# BlackKnight.net
KiCad netlist of a schematic drawn in EAGLE
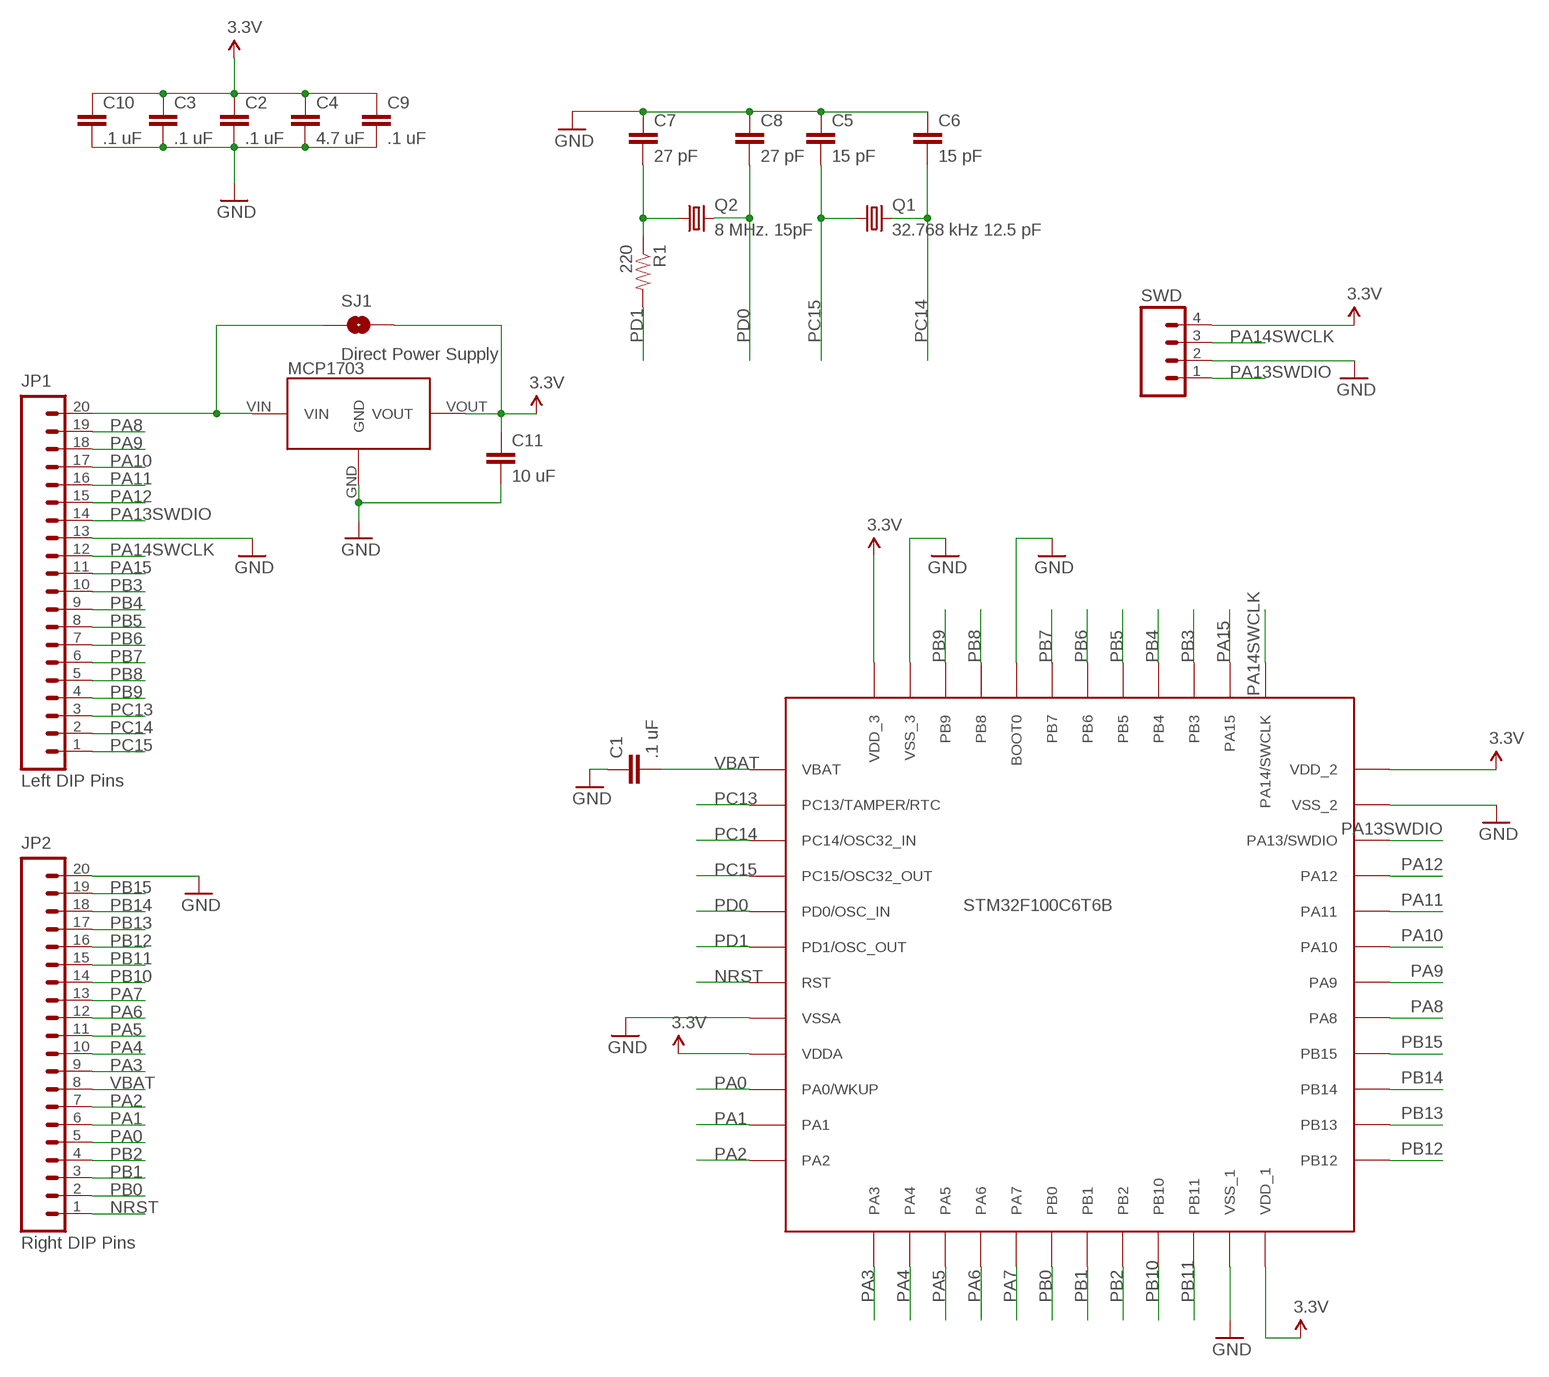
[diagram p0: schematic, sheet 1]

(export (version "E")
  (design (tool "Eeschema 10.0.6"))
  (components
    (comp (ref "C1")
      (value ".1 uF")
      (footprint "eagle-import:0805")
      (libsource (lib "eagle-import") (part "1.0UF-25V-+80/-20(0805)"))
    )
    (comp (ref "C2")
      (value ".1 uF")
      (footprint "eagle-import:0805")
      (libsource (lib "eagle-import") (part "1.0UF-25V-+80/-20(0805)"))
    )
    (comp (ref "C3")
      (value ".1 uF")
      (footprint "eagle-import:0805")
      (libsource (lib "eagle-import") (part "1.0UF-25V-+80/-20(0805)"))
    )
    (comp (ref "C4")
      (value "4.7 uF")
      (footprint "eagle-import:0805")
      (libsource (lib "eagle-import") (part "1.0UF-25V-+80/-20(0805)"))
    )
    (comp (ref "C5")
      (value "15 pF")
      (footprint "eagle-import:0805")
      (libsource (lib "eagle-import") (part "1.0UF-25V-+80/-20(0805)"))
    )
    (comp (ref "C6")
      (value "15 pF")
      (footprint "eagle-import:0805")
      (libsource (lib "eagle-import") (part "1.0UF-25V-+80/-20(0805)"))
    )
    (comp (ref "C7")
      (value "27 pF")
      (footprint "eagle-import:0805")
      (libsource (lib "eagle-import") (part "1.0UF-25V-+80/-20(0805)"))
    )
    (comp (ref "C8")
      (value "27 pF")
      (footprint "eagle-import:0805")
      (libsource (lib "eagle-import") (part "1.0UF-25V-+80/-20(0805)"))
    )
    (comp (ref "C9")
      (value ".1 uF")
      (footprint "eagle-import:0805")
      (libsource (lib "eagle-import") (part "1.0UF-25V-+80/-20(0805)"))
    )
    (comp (ref "C10")
      (value ".1 uF")
      (footprint "eagle-import:0805")
      (libsource (lib "eagle-import") (part "1.0UF-25V-+80/-20(0805)"))
    )
    (comp (ref "C11")
      (value "10 uF")
      (footprint "eagle-import:0805")
      (libsource (lib "eagle-import") (part "1.0UF-25V-+80/-20(0805)"))
    )
    (comp (ref "JP1")
      (value "Left DIP Pins")
      (footprint "eagle-import:1X20")
      (libsource (lib "eagle-import") (part "M20"))
    )
    (comp (ref "JP2")
      (value "Right DIP Pins")
      (footprint "eagle-import:1X20")
      (libsource (lib "eagle-import") (part "M20"))
    )
    (comp (ref "MCP1703")
      (value "MCP1703")
      (footprint "eagle-import:SOT-89")
      (libsource (lib "eagle-import") (part "MCP1703"))
    )
    (comp (ref "Q1")
      (value "32.768 kHz 12.5 pF")
      (footprint "eagle-import:TC26H")
      (libsource (lib "eagle-import") (part "CRYSTALTC26H"))
    )
    (comp (ref "Q2")
      (value "8 MHz. 15pF")
      (footprint "eagle-import:HC49U-V")
      (libsource (lib "eagle-import") (part "CRYSTALHC49U-V"))
    )
    (comp (ref "R1")
      (value "220")
      (footprint "eagle-import:0805")
      (libsource (lib "eagle-import") (part "RESISTOR0805-RES"))
    )
    (comp (ref "SJ1")
      (value "Direct Power Supply")
      (footprint "eagle-import:SJ_2S-NO")
      (libsource (lib "eagle-import") (part "SOLDERJUMPER-OLDNO"))
    )
    (comp (ref "STM32F100C6T6B")
      (value "STM32F100C6T6B")
      (footprint "eagle-import:48-LQFP")
      (libsource (lib "eagle-import") (part "STM32F100C6T6B"))
    )
    (comp (ref "SWD")
      (value "M04LOCK")
      (footprint "eagle-import:1X04_LOCK")
      (libsource (lib "eagle-import") (part "M04LOCK"))
    )
  )
  (nets
    (net (code "1") (name "/NRST") (class "Default")
      (node (ref "JP2") (pin "1") (pinfunction "1_1") (pintype "passive"))
      (node (ref "STM32F100C6T6B") (pin "RST") (pinfunction "RST_RST") (pintype "bidirectional"))
    )
    (net (code "2") (name "/PA0") (class "Default")
      (node (ref "JP2") (pin "5") (pinfunction "5_5") (pintype "passive"))
      (node (ref "STM32F100C6T6B") (pin "PA0/WKUP") (pinfunction "PA0/WKUP_PA0/WKUP") (pintype "bidirectional"))
    )
    (net (code "3") (name "/PA1") (class "Default")
      (node (ref "JP2") (pin "6") (pinfunction "6_6") (pintype "passive"))
      (node (ref "STM32F100C6T6B") (pin "PA1") (pinfunction "PA1_PA1") (pintype "bidirectional"))
    )
    (net (code "4") (name "/PA2") (class "Default")
      (node (ref "JP2") (pin "7") (pinfunction "7_7") (pintype "passive"))
      (node (ref "STM32F100C6T6B") (pin "PA2") (pinfunction "PA2_PA2") (pintype "bidirectional"))
    )
    (net (code "5") (name "/PA3") (class "Default")
      (node (ref "JP2") (pin "9") (pinfunction "9_9") (pintype "passive"))
      (node (ref "STM32F100C6T6B") (pin "PA3") (pinfunction "PA3_PA3") (pintype "bidirectional"))
    )
    (net (code "6") (name "/PA4") (class "Default")
      (node (ref "JP2") (pin "10") (pinfunction "10_10") (pintype "passive"))
      (node (ref "STM32F100C6T6B") (pin "PA4") (pinfunction "PA4_PA4") (pintype "bidirectional"))
    )
    (net (code "7") (name "/PA5") (class "Default")
      (node (ref "JP2") (pin "11") (pinfunction "11_11") (pintype "passive"))
      (node (ref "STM32F100C6T6B") (pin "PA5") (pinfunction "PA5_PA5") (pintype "bidirectional"))
    )
    (net (code "8") (name "/PA6") (class "Default")
      (node (ref "JP2") (pin "12") (pinfunction "12_12") (pintype "passive"))
      (node (ref "STM32F100C6T6B") (pin "PA6") (pinfunction "PA6_PA6") (pintype "bidirectional"))
    )
    (net (code "9") (name "/PA7") (class "Default")
      (node (ref "JP2") (pin "13") (pinfunction "13_13") (pintype "passive"))
      (node (ref "STM32F100C6T6B") (pin "PA7") (pinfunction "PA7_PA7") (pintype "bidirectional"))
    )
    (net (code "10") (name "/PA8") (class "Default")
      (node (ref "JP1") (pin "19") (pinfunction "19_19") (pintype "passive"))
      (node (ref "STM32F100C6T6B") (pin "PA8") (pinfunction "PA8_PA8") (pintype "bidirectional"))
    )
    (net (code "11") (name "/PA9") (class "Default")
      (node (ref "JP1") (pin "18") (pinfunction "18_18") (pintype "passive"))
      (node (ref "STM32F100C6T6B") (pin "PA9") (pinfunction "PA9_PA9") (pintype "bidirectional"))
    )
    (net (code "12") (name "/PA10") (class "Default")
      (node (ref "JP1") (pin "17") (pinfunction "17_17") (pintype "passive"))
      (node (ref "STM32F100C6T6B") (pin "PA10") (pinfunction "PA10_PA10") (pintype "bidirectional"))
    )
    (net (code "13") (name "/PA11") (class "Default")
      (node (ref "JP1") (pin "16") (pinfunction "16_16") (pintype "passive"))
      (node (ref "STM32F100C6T6B") (pin "PA11") (pinfunction "PA11_PA11") (pintype "bidirectional"))
    )
    (net (code "14") (name "/PA12") (class "Default")
      (node (ref "JP1") (pin "15") (pinfunction "15_15") (pintype "passive"))
      (node (ref "STM32F100C6T6B") (pin "PA12") (pinfunction "PA12_PA12") (pintype "bidirectional"))
    )
    (net (code "15") (name "/PA13SWDIO") (class "Default")
      (node (ref "JP1") (pin "14") (pinfunction "14_14") (pintype "passive"))
      (node (ref "STM32F100C6T6B") (pin "PA13/SWDIO") (pinfunction "PA13/SWDIO_PA13/SWDIO") (pintype "bidirectional"))
      (node (ref "SWD") (pin "1") (pinfunction "1_1") (pintype "passive"))
    )
    (net (code "16") (name "/PA14SWCLK") (class "Default")
      (node (ref "JP1") (pin "12") (pinfunction "12_12") (pintype "passive"))
      (node (ref "STM32F100C6T6B") (pin "PA14/SWCLK") (pinfunction "PA14/SWCLK_PA14/SWCLK") (pintype "bidirectional"))
      (node (ref "SWD") (pin "3") (pinfunction "3_3") (pintype "passive"))
    )
    (net (code "17") (name "/PA15") (class "Default")
      (node (ref "JP1") (pin "11") (pinfunction "11_11") (pintype "passive"))
      (node (ref "STM32F100C6T6B") (pin "PA15") (pinfunction "PA15_PA15") (pintype "bidirectional"))
    )
    (net (code "18") (name "/PB0") (class "Default")
      (node (ref "JP2") (pin "2") (pinfunction "2_2") (pintype "passive"))
      (node (ref "STM32F100C6T6B") (pin "PB0") (pinfunction "PB0_PB0") (pintype "bidirectional"))
    )
    (net (code "19") (name "/PB1") (class "Default")
      (node (ref "JP2") (pin "3") (pinfunction "3_3") (pintype "passive"))
      (node (ref "STM32F100C6T6B") (pin "PB1") (pinfunction "PB1_PB1") (pintype "bidirectional"))
    )
    (net (code "20") (name "/PB2") (class "Default")
      (node (ref "JP2") (pin "4") (pinfunction "4_4") (pintype "passive"))
      (node (ref "STM32F100C6T6B") (pin "PB2") (pinfunction "PB2_PB2") (pintype "bidirectional"))
    )
    (net (code "21") (name "/PB3") (class "Default")
      (node (ref "JP1") (pin "10") (pinfunction "10_10") (pintype "passive"))
      (node (ref "STM32F100C6T6B") (pin "PB3") (pinfunction "PB3_PB3") (pintype "bidirectional"))
    )
    (net (code "22") (name "/PB4") (class "Default")
      (node (ref "JP1") (pin "9") (pinfunction "9_9") (pintype "passive"))
      (node (ref "STM32F100C6T6B") (pin "PB4") (pinfunction "PB4_PB4") (pintype "bidirectional"))
    )
    (net (code "23") (name "/PB5") (class "Default")
      (node (ref "JP1") (pin "8") (pinfunction "8_8") (pintype "passive"))
      (node (ref "STM32F100C6T6B") (pin "PB5") (pinfunction "PB5_PB5") (pintype "bidirectional"))
    )
    (net (code "24") (name "/PB6") (class "Default")
      (node (ref "JP1") (pin "7") (pinfunction "7_7") (pintype "passive"))
      (node (ref "STM32F100C6T6B") (pin "PB6") (pinfunction "PB6_PB6") (pintype "bidirectional"))
    )
    (net (code "25") (name "/PB7") (class "Default")
      (node (ref "JP1") (pin "6") (pinfunction "6_6") (pintype "passive"))
      (node (ref "STM32F100C6T6B") (pin "PB7") (pinfunction "PB7_PB7") (pintype "bidirectional"))
    )
    (net (code "26") (name "/PB8") (class "Default")
      (node (ref "JP1") (pin "5") (pinfunction "5_5") (pintype "passive"))
      (node (ref "STM32F100C6T6B") (pin "PB8") (pinfunction "PB8_PB8") (pintype "bidirectional"))
    )
    (net (code "27") (name "/PB9") (class "Default")
      (node (ref "JP1") (pin "4") (pinfunction "4_4") (pintype "passive"))
      (node (ref "STM32F100C6T6B") (pin "PB9") (pinfunction "PB9_PB9") (pintype "bidirectional"))
    )
    (net (code "28") (name "/PB10") (class "Default")
      (node (ref "JP2") (pin "14") (pinfunction "14_14") (pintype "passive"))
      (node (ref "STM32F100C6T6B") (pin "PB10") (pinfunction "PB10_PB10") (pintype "bidirectional"))
    )
    (net (code "29") (name "/PB11") (class "Default")
      (node (ref "JP2") (pin "15") (pinfunction "15_15") (pintype "passive"))
      (node (ref "STM32F100C6T6B") (pin "PB11") (pinfunction "PB11_PB11") (pintype "bidirectional"))
    )
    (net (code "30") (name "/PB12") (class "Default")
      (node (ref "JP2") (pin "16") (pinfunction "16_16") (pintype "passive"))
      (node (ref "STM32F100C6T6B") (pin "PB12") (pinfunction "PB12_PB12") (pintype "bidirectional"))
    )
    (net (code "31") (name "/PB13") (class "Default")
      (node (ref "JP2") (pin "17") (pinfunction "17_17") (pintype "passive"))
      (node (ref "STM32F100C6T6B") (pin "PB13") (pinfunction "PB13_PB13") (pintype "bidirectional"))
    )
    (net (code "32") (name "/PB14") (class "Default")
      (node (ref "JP2") (pin "18") (pinfunction "18_18") (pintype "passive"))
      (node (ref "STM32F100C6T6B") (pin "PB14") (pinfunction "PB14_PB14") (pintype "bidirectional"))
    )
    (net (code "33") (name "/PB15") (class "Default")
      (node (ref "JP2") (pin "19") (pinfunction "19_19") (pintype "passive"))
      (node (ref "STM32F100C6T6B") (pin "PB15") (pinfunction "PB15_PB15") (pintype "bidirectional"))
    )
    (net (code "34") (name "/PC13") (class "Default")
      (node (ref "JP1") (pin "3") (pinfunction "3_3") (pintype "passive"))
      (node (ref "STM32F100C6T6B") (pin "PC13/TAMPER/RTC") (pinfunction "PC13/TAMPER/RTC_PC13/TAMPER/RTC") (pintype "bidirectional"))
    )
    (net (code "35") (name "/PC14") (class "Default")
      (node (ref "C6") (pin "2") (pinfunction "2_2") (pintype "passive"))
      (node (ref "JP1") (pin "2") (pinfunction "2_2") (pintype "passive"))
      (node (ref "Q1") (pin "2") (pinfunction "2_2") (pintype "passive"))
      (node (ref "STM32F100C6T6B") (pin "PC14/OSC32_IN") (pinfunction "PC14/OSC32_IN_PC14/OSC32_IN") (pintype "bidirectional"))
    )
    (net (code "36") (name "/PC15") (class "Default")
      (node (ref "C5") (pin "2") (pinfunction "2_2") (pintype "passive"))
      (node (ref "JP1") (pin "1") (pinfunction "1_1") (pintype "passive"))
      (node (ref "Q1") (pin "1") (pinfunction "1_1") (pintype "passive"))
      (node (ref "STM32F100C6T6B") (pin "PC15/OSC32_OUT") (pinfunction "PC15/OSC32_OUT_PC15/OSC32_OUT") (pintype "bidirectional"))
    )
    (net (code "37") (name "/PD0") (class "Default")
      (node (ref "C8") (pin "2") (pinfunction "2_2") (pintype "passive"))
      (node (ref "Q2") (pin "2") (pinfunction "2_2") (pintype "passive"))
      (node (ref "STM32F100C6T6B") (pin "PD0/OSC_IN") (pinfunction "PD0/OSC_IN_PD0/OSC_IN") (pintype "bidirectional"))
    )
    (net (code "38") (name "/PD1") (class "Default")
      (node (ref "R1") (pin "2") (pinfunction "2_2") (pintype "passive"))
      (node (ref "STM32F100C6T6B") (pin "PD1/OSC_OUT") (pinfunction "PD1/OSC_OUT_PD1/OSC_OUT") (pintype "bidirectional"))
    )
    (net (code "39") (name "/VBAT") (class "Default")
      (node (ref "C1") (pin "2") (pinfunction "2_2") (pintype "passive"))
      (node (ref "JP2") (pin "8") (pinfunction "8_8") (pintype "passive"))
      (node (ref "STM32F100C6T6B") (pin "VBAT") (pinfunction "VBAT_VBAT") (pintype "bidirectional"))
    )
    (net (code "40") (name "3.3V") (class "Default")
      (node (ref "C10") (pin "1") (pinfunction "1_1") (pintype "passive"))
      (node (ref "C11") (pin "1") (pinfunction "1_1") (pintype "passive"))
      (node (ref "C2") (pin "1") (pinfunction "1_1") (pintype "passive"))
      (node (ref "C3") (pin "1") (pinfunction "1_1") (pintype "passive"))
      (node (ref "C4") (pin "1") (pinfunction "1_1") (pintype "passive"))
      (node (ref "C9") (pin "1") (pinfunction "1_1") (pintype "passive"))
      (node (ref "MCP1703") (pin "VOUT") (pinfunction "VOUT_VOUT") (pintype "bidirectional"))
      (node (ref "SJ1") (pin "2") (pinfunction "2_2") (pintype "passive"))
      (node (ref "STM32F100C6T6B") (pin "VDDA") (pinfunction "VDDA_VDDA") (pintype "bidirectional"))
      (node (ref "STM32F100C6T6B") (pin "VDD_1") (pinfunction "VDD_1_VDD_1") (pintype "bidirectional"))
      (node (ref "STM32F100C6T6B") (pin "VDD_2") (pinfunction "VDD_2_VDD_2") (pintype "bidirectional"))
      (node (ref "STM32F100C6T6B") (pin "VDD_3") (pinfunction "VDD_3_VDD_3") (pintype "bidirectional"))
      (node (ref "SWD") (pin "4") (pinfunction "4_4") (pintype "passive"))
    )
    (net (code "41") (name "GND") (class "Default")
      (node (ref "C1") (pin "1") (pinfunction "1_1") (pintype "passive"))
      (node (ref "C10") (pin "2") (pinfunction "2_2") (pintype "passive"))
      (node (ref "C11") (pin "2") (pinfunction "2_2") (pintype "passive"))
      (node (ref "C2") (pin "2") (pinfunction "2_2") (pintype "passive"))
      (node (ref "C3") (pin "2") (pinfunction "2_2") (pintype "passive"))
      (node (ref "C4") (pin "2") (pinfunction "2_2") (pintype "passive"))
      (node (ref "C5") (pin "1") (pinfunction "1_1") (pintype "passive"))
      (node (ref "C6") (pin "1") (pinfunction "1_1") (pintype "passive"))
      (node (ref "C7") (pin "1") (pinfunction "1_1") (pintype "passive"))
      (node (ref "C8") (pin "1") (pinfunction "1_1") (pintype "passive"))
      (node (ref "C9") (pin "2") (pinfunction "2_2") (pintype "passive"))
      (node (ref "JP1") (pin "13") (pinfunction "13_13") (pintype "passive"))
      (node (ref "JP2") (pin "20") (pinfunction "20_20") (pintype "passive"))
      (node (ref "MCP1703") (pin "GND") (pinfunction "GND_GND") (pintype "bidirectional"))
      (node (ref "STM32F100C6T6B") (pin "BOOT0") (pinfunction "BOOT0_BOOT0") (pintype "bidirectional"))
      (node (ref "STM32F100C6T6B") (pin "VSSA") (pinfunction "VSSA_VSSA") (pintype "bidirectional"))
      (node (ref "STM32F100C6T6B") (pin "VSS_1") (pinfunction "VSS_1_VSS_1") (pintype "bidirectional"))
      (node (ref "STM32F100C6T6B") (pin "VSS_2") (pinfunction "VSS_2_VSS_2") (pintype "bidirectional"))
      (node (ref "STM32F100C6T6B") (pin "VSS_3") (pinfunction "VSS_3_VSS_3") (pintype "bidirectional"))
      (node (ref "SWD") (pin "2") (pinfunction "2_2") (pintype "passive"))
    )
    (net (code "42") (name "Net-(C7-Pad2)") (class "Default")
      (node (ref "C7") (pin "2") (pinfunction "2_2") (pintype "passive"))
      (node (ref "Q2") (pin "1") (pinfunction "1_1") (pintype "passive"))
      (node (ref "R1") (pin "1") (pinfunction "1_1") (pintype "passive"))
    )
    (net (code "43") (name "Net-(JP1-Pad20)") (class "Default")
      (node (ref "JP1") (pin "20") (pinfunction "20_20") (pintype "passive"))
      (node (ref "MCP1703") (pin "VIN") (pinfunction "VIN_VIN") (pintype "bidirectional"))
      (node (ref "SJ1") (pin "1") (pinfunction "1_1") (pintype "passive"))
    )
  )
)
